# D2D-TOP.net
KiCad netlist of a schematic drawn in EAGLE
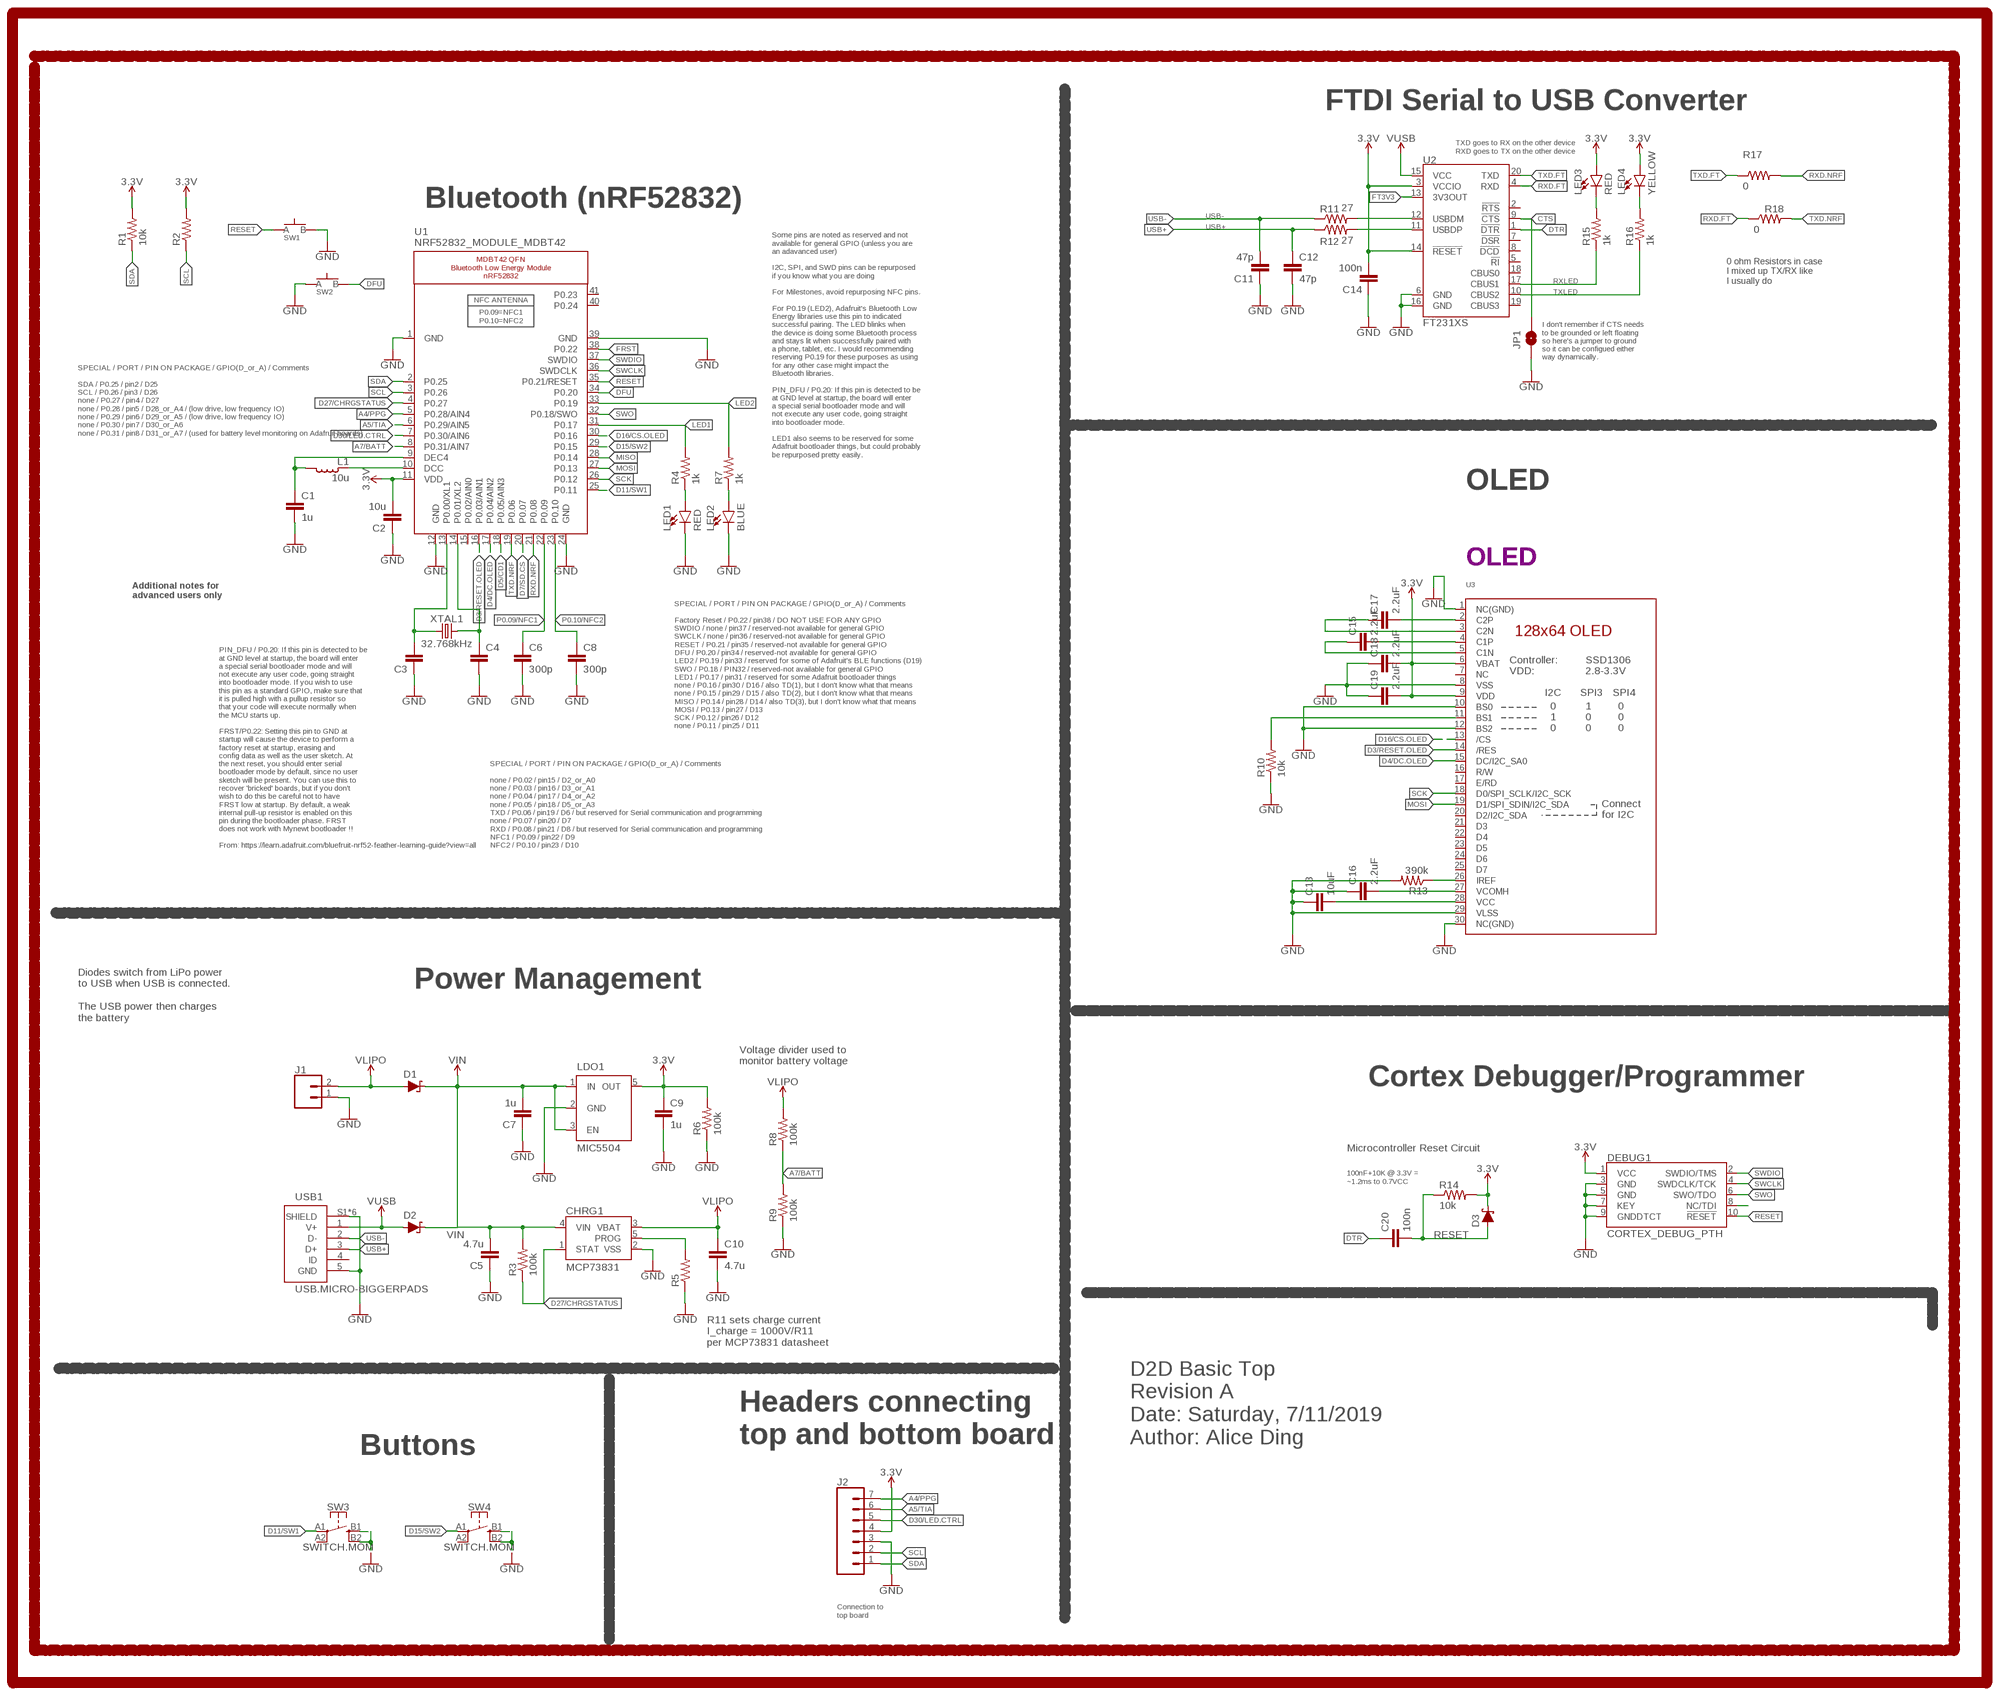
[diagram p0: schematic, sheet 1]

(export (version "E")
  (design (tool "Eeschema 10.0.6"))
  (components
    (comp (ref "C1")
      (value "1u")
      (footprint "eagle-import:C0603")
      (libsource (lib "eagle-import") (part "CAPACITOR0603"))
    )
    (comp (ref "C2")
      (value "10u")
      (footprint "eagle-import:C0805")
      (libsource (lib "eagle-import") (part "CAPACITOR0805"))
    )
    (comp (ref "C3")
      (value "CAPACITOR0603")
      (footprint "eagle-import:C0603")
      (libsource (lib "eagle-import") (part "CAPACITOR0603"))
    )
    (comp (ref "C4")
      (value "CAPACITOR0603")
      (footprint "eagle-import:C0603")
      (libsource (lib "eagle-import") (part "CAPACITOR0603"))
    )
    (comp (ref "C5")
      (value "4.7u")
      (footprint "eagle-import:C0603")
      (libsource (lib "eagle-import") (part "CAPACITOR0603"))
    )
    (comp (ref "C6")
      (value "300p")
      (footprint "eagle-import:C0603")
      (libsource (lib "eagle-import") (part "CAPACITOR0603"))
    )
    (comp (ref "C7")
      (value "1u")
      (footprint "eagle-import:C0603")
      (libsource (lib "eagle-import") (part "CAPACITOR0603"))
    )
    (comp (ref "C8")
      (value "300p")
      (footprint "eagle-import:C0603")
      (libsource (lib "eagle-import") (part "CAPACITOR0603"))
    )
    (comp (ref "C9")
      (value "1u")
      (footprint "eagle-import:C0603")
      (libsource (lib "eagle-import") (part "CAPACITOR0603"))
    )
    (comp (ref "C10")
      (value "4.7u")
      (footprint "eagle-import:C0603")
      (libsource (lib "eagle-import") (part "CAPACITOR0603"))
    )
    (comp (ref "C11")
      (value "47p")
      (footprint "eagle-import:C0603")
      (libsource (lib "eagle-import") (part "CAPACITOR0603"))
    )
    (comp (ref "C12")
      (value "47p")
      (footprint "eagle-import:C0603")
      (libsource (lib "eagle-import") (part "CAPACITOR0603"))
    )
    (comp (ref "C13")
      (value "10uF")
      (footprint "eagle-import:C0603")
      (libsource (lib "eagle-import") (part "CAPACITOR0603"))
    )
    (comp (ref "C14")
      (value "100n")
      (footprint "eagle-import:C0603")
      (libsource (lib "eagle-import") (part "CAPACITOR0603"))
    )
    (comp (ref "C15")
      (value "2.2uF")
      (footprint "eagle-import:C0402")
      (libsource (lib "eagle-import") (part "CAPACITOR0402"))
    )
    (comp (ref "C16")
      (value "2.2uF")
      (footprint "eagle-import:C0402")
      (libsource (lib "eagle-import") (part "CAPACITOR0402"))
    )
    (comp (ref "C17")
      (value "2.2uF")
      (footprint "eagle-import:C0402")
      (libsource (lib "eagle-import") (part "CAPACITOR0402"))
    )
    (comp (ref "C18")
      (value "2.2uF")
      (footprint "eagle-import:C0402")
      (libsource (lib "eagle-import") (part "CAPACITOR0402"))
    )
    (comp (ref "C19")
      (value "2.2uF")
      (footprint "eagle-import:C0402")
      (libsource (lib "eagle-import") (part "CAPACITOR0402"))
    )
    (comp (ref "C20")
      (value "100n")
      (footprint "eagle-import:C0603")
      (libsource (lib "eagle-import") (part "CAPACITOR0603"))
    )
    (comp (ref "CHRG1")
      (value "MCP73831")
      (footprint "eagle-import:SOT23-5")
      (libsource (lib "eagle-import") (part "MCP73831"))
    )
    (comp (ref "D1")
      (value "SCHOTTKY-USC")
      (footprint "eagle-import:USC")
      (libsource (lib "eagle-import") (part "SCHOTTKY-USC"))
    )
    (comp (ref "D2")
      (value "SCHOTTKY-USC")
      (footprint "eagle-import:USC")
      (libsource (lib "eagle-import") (part "SCHOTTKY-USC"))
    )
    (comp (ref "D3")
      (value "SCHOTTKY-USC")
      (footprint "eagle-import:USC")
      (libsource (lib "eagle-import") (part "SCHOTTKY-USC"))
    )
    (comp (ref "DEBUG1")
      (value "CORTEX_DEBUG_PTH")
      (footprint "eagle-import:2X5-PTH-1.27MM")
      (libsource (lib "eagle-import") (part "CORTEX_DEBUG_PTH"))
    )
    (comp (ref "J1")
      (value "CONN_02")
      (footprint "eagle-import:1X02")
      (libsource (lib "eagle-import") (part "CONN_02"))
    )
    (comp (ref "J2")
      (value "CONN_07-1.27MM")
      (footprint "eagle-import:1X07_1.27MM")
      (libsource (lib "eagle-import") (part "CONN_07-1.27MM"))
    )
    (comp (ref "JP1")
      (value "JUMPER-SMT_2_NO_SILK")
      (footprint "eagle-import:SMT-JUMPER_2_NO_SILK")
      (libsource (lib "eagle-import") (part "JUMPER-SMT_2_NO_SILK"))
    )
    (comp (ref "L1")
      (value "10u")
      (footprint "eagle-import:L0603")
      (libsource (lib "eagle-import") (part "INDUCTOR0603"))
    )
    (comp (ref "LDO1")
      (value "MIC5504")
      (footprint "eagle-import:SOT23-5")
      (libsource (lib "eagle-import") (part "MIC5504"))
    )
    (comp (ref "LED1")
      (value "RED")
      (footprint "eagle-import:LED-0603")
      (libsource (lib "eagle-import") (part "LED0603"))
    )
    (comp (ref "LED2")
      (value "BLUE")
      (footprint "eagle-import:LED-0603")
      (libsource (lib "eagle-import") (part "LED0603"))
    )
    (comp (ref "LED3")
      (value "RED")
      (footprint "eagle-import:LED-0603")
      (libsource (lib "eagle-import") (part "LED0603"))
    )
    (comp (ref "LED4")
      (value "YELLOW")
      (footprint "eagle-import:LED-0603")
      (libsource (lib "eagle-import") (part "LED0603"))
    )
    (comp (ref "R1")
      (value "10k")
      (footprint "eagle-import:R0603")
      (libsource (lib "eagle-import") (part "RESISTOR0603"))
    )
    (comp (ref "R2")
      (value "RESISTOR0603")
      (footprint "eagle-import:R0603")
      (libsource (lib "eagle-import") (part "RESISTOR0603"))
    )
    (comp (ref "R3")
      (value "100k")
      (footprint "eagle-import:R0603")
      (libsource (lib "eagle-import") (part "RESISTOR0603"))
    )
    (comp (ref "R4")
      (value "1k")
      (footprint "eagle-import:R0603")
      (libsource (lib "eagle-import") (part "RESISTOR0603"))
    )
    (comp (ref "R5")
      (value "RESISTOR0603")
      (footprint "eagle-import:R0603")
      (libsource (lib "eagle-import") (part "RESISTOR0603"))
    )
    (comp (ref "R6")
      (value "100k")
      (footprint "eagle-import:R0603")
      (libsource (lib "eagle-import") (part "RESISTOR0603"))
    )
    (comp (ref "R7")
      (value "1k")
      (footprint "eagle-import:R0603")
      (libsource (lib "eagle-import") (part "RESISTOR0603"))
    )
    (comp (ref "R8")
      (value "100k")
      (footprint "eagle-import:R0603")
      (libsource (lib "eagle-import") (part "RESISTOR0603"))
    )
    (comp (ref "R9")
      (value "100k")
      (footprint "eagle-import:R0603")
      (libsource (lib "eagle-import") (part "RESISTOR0603"))
    )
    (comp (ref "R10")
      (value "10k")
      (footprint "eagle-import:R0603")
      (libsource (lib "eagle-import") (part "RESISTOR0603"))
    )
    (comp (ref "R11")
      (value "27")
      (footprint "eagle-import:R0603")
      (libsource (lib "eagle-import") (part "RESISTOR0603"))
    )
    (comp (ref "R12")
      (value "27")
      (footprint "eagle-import:R0603")
      (libsource (lib "eagle-import") (part "RESISTOR0603"))
    )
    (comp (ref "R13")
      (value "390k")
      (footprint "eagle-import:R0603")
      (libsource (lib "eagle-import") (part "RESISTOR0603"))
    )
    (comp (ref "R14")
      (value "10k")
      (footprint "eagle-import:R0603")
      (libsource (lib "eagle-import") (part "RESISTOR0603"))
    )
    (comp (ref "R15")
      (value "1k")
      (footprint "eagle-import:R0603")
      (libsource (lib "eagle-import") (part "RESISTOR0603"))
    )
    (comp (ref "R16")
      (value "1k")
      (footprint "eagle-import:R0603")
      (libsource (lib "eagle-import") (part "RESISTOR0603"))
    )
    (comp (ref "R17")
      (value "0")
      (footprint "eagle-import:R0603")
      (libsource (lib "eagle-import") (part "RESISTOR0603"))
    )
    (comp (ref "R18")
      (value "0")
      (footprint "eagle-import:R0603")
      (libsource (lib "eagle-import") (part "RESISTOR0603"))
    )
    (comp (ref "SW1")
      (value "SPST-PTS830GG140-COPY.1-3")
      (footprint "eagle-import:BUTTON-GULLWING")
      (libsource (lib "eagle-import") (part "SPST-PTS830GG140-COPY.1-3"))
    )
    (comp (ref "SW2")
      (value "SPST-PTS830GG140-COPY.1-3")
      (footprint "eagle-import:BUTTON-GULLWING")
      (libsource (lib "eagle-import") (part "SPST-PTS830GG140-COPY.1-3"))
    )
    (comp (ref "SW3")
      (value "SWITCH.MOM")
      (footprint "eagle-import:TACTILE_SWITCH_SMD_6.2MM_TALL")
      (libsource (lib "eagle-import") (part "SWITCH.MOM"))
    )
    (comp (ref "SW4")
      (value "SWITCH.MOM")
      (footprint "eagle-import:TACTILE_SWITCH_SMD_6.2MM_TALL")
      (libsource (lib "eagle-import") (part "SWITCH.MOM"))
    )
    (comp (ref "U1")
      (value "NRF52832_MODULE_MDBT42")
      (footprint "eagle-import:BLE_MODULE_RAYTAC_MDBT42")
      (libsource (lib "eagle-import") (part "NRF52832_MODULE_MDBT42"))
    )
    (comp (ref "U2")
      (value "FT231XS")
      (footprint "eagle-import:SSOP20_L")
      (libsource (lib "eagle-import") (part "FT231XS"))
    )
    (comp (ref "U3")
      (value "DISP_OLED_UG-2864HSWEG01-NO-WRAPAROUND")
      (footprint "eagle-import:UG-2864HSWEG01_0.96IN_NO-WRAPAROUND")
      (libsource (lib "eagle-import") (part "DISP_OLED_UG-2864HSWEG01-NO-WRAPAROUND"))
    )
    (comp (ref "USB1")
      (value "USB.MICRO-BIGGERPADS")
      (footprint "eagle-import:USB-MICRO-01.BIGGERPADS")
      (libsource (lib "eagle-import") (part "USB.MICRO-BIGGERPADS"))
    )
    (comp (ref "XTAL1")
      (value "32.768kHz")
      (footprint "eagle-import:2-SMD.NOLEAD.2.0MMTO1.2MM")
      (libsource (lib "eagle-import") (part "CRYSTALECS-.327-12.5-12-C-TR"))
    )
  )
  (nets
    (net (code "1") (name "/RXLED") (class "Default")
      (node (ref "R15") (pin "1") (pinfunction "1_1") (pintype "passive"))
      (node (ref "U2") (pin "17") (pinfunction "CBUS1_17") (pintype "bidirectional"))
    )
    (net (code "2") (name "/TXLED") (class "Default")
      (node (ref "R16") (pin "1") (pinfunction "1_1") (pintype "passive"))
      (node (ref "U2") (pin "10") (pinfunction "CBUS2_10") (pintype "bidirectional"))
    )
    (net (code "3") (name "3.3V") (class "Default")
      (node (ref "C14") (pin "2") (pinfunction "2_2") (pintype "passive"))
      (node (ref "C18") (pin "2") (pinfunction "2_2") (pintype "passive"))
      (node (ref "C19") (pin "2") (pinfunction "2_2") (pintype "passive"))
      (node (ref "C2") (pin "2") (pinfunction "2_2") (pintype "passive"))
      (node (ref "C9") (pin "1") (pinfunction "1_1") (pintype "passive"))
      (node (ref "D3") (pin "-") (pinfunction "C_-") (pintype "passive"))
      (node (ref "DEBUG1") (pin "1") (pinfunction "VCC_1") (pintype "bidirectional"))
      (node (ref "J2") (pin "4") (pinfunction "4_4") (pintype "passive"))
      (node (ref "LDO1") (pin "5") (pinfunction "OUT_5") (pintype "bidirectional"))
      (node (ref "LED3") (pin "A") (pinfunction "A_A") (pintype "passive"))
      (node (ref "LED4") (pin "A") (pinfunction "A_A") (pintype "passive"))
      (node (ref "R1") (pin "2") (pinfunction "2_2") (pintype "passive"))
      (node (ref "R14") (pin "2") (pinfunction "2_2") (pintype "passive"))
      (node (ref "R2") (pin "2") (pinfunction "2_2") (pintype "passive"))
      (node (ref "R6") (pin "2") (pinfunction "2_2") (pintype "passive"))
      (node (ref "U1") (pin "11") (pinfunction "VDD_11") (pintype "bidirectional"))
      (node (ref "U2") (pin "14") (pinfunction "~{RESET}_14") (pintype "bidirectional"))
      (node (ref "U2") (pin "3") (pinfunction "VCCIO_3") (pintype "bidirectional"))
      (node (ref "U3") (pin "6") (pinfunction "VBAT_6") (pintype "input"))
      (node (ref "U3") (pin "9") (pinfunction "VDD_9") (pintype "power_in"))
    )
    (net (code "4") (name "A4{slash}PPG") (class "Default")
      (node (ref "J2") (pin "7") (pinfunction "7_7") (pintype "passive"))
      (node (ref "U1") (pin "5") (pinfunction "P0.28/AIN4_5") (pintype "bidirectional"))
    )
    (net (code "5") (name "A5{slash}TIA") (class "Default")
      (node (ref "J2") (pin "6") (pinfunction "6_6") (pintype "passive"))
      (node (ref "U1") (pin "6") (pinfunction "P0.29/AIN5_6") (pintype "bidirectional"))
    )
    (net (code "6") (name "A7{slash}BATT") (class "Default")
      (node (ref "R8") (pin "1") (pinfunction "1_1") (pintype "passive"))
      (node (ref "R9") (pin "2") (pinfunction "2_2") (pintype "passive"))
      (node (ref "U1") (pin "8") (pinfunction "P0.31/AIN7_8") (pintype "bidirectional"))
    )
    (net (code "7") (name "CTS") (class "Default")
      (node (ref "JP1") (pin "2") (pinfunction "2_2") (pintype "passive"))
      (node (ref "U2") (pin "9") (pinfunction "~{CTS}_9") (pintype "bidirectional"))
    )
    (net (code "8") (name "D3{slash}RESET.OLED") (class "Default")
      (node (ref "U1") (pin "16") (pinfunction "P0.03/AIN1_16") (pintype "bidirectional"))
      (node (ref "U3") (pin "14") (pinfunction "/RES_14") (pintype "input"))
    )
    (net (code "9") (name "D4{slash}DC.OLED") (class "Default")
      (node (ref "U1") (pin "17") (pinfunction "P0.04/AIN2_17") (pintype "bidirectional"))
      (node (ref "U3") (pin "15") (pinfunction "DC/I2C_SA0_15") (pintype "input"))
    )
    (net (code "10") (name "D5{slash}CD1") (class "Default")
      (node (ref "U1") (pin "18") (pinfunction "P0.05/AIN3_18") (pintype "bidirectional"))
    )
    (net (code "11") (name "D7{slash}SD.CS") (class "Default")
      (node (ref "U1") (pin "20") (pinfunction "P0.07_20") (pintype "bidirectional"))
    )
    (net (code "12") (name "D11{slash}SW1") (class "Default")
      (node (ref "SW3") (pin "A1") (pinfunction "1_A1") (pintype "passive"))
      (node (ref "U1") (pin "25") (pinfunction "P0.11_25") (pintype "bidirectional"))
    )
    (net (code "13") (name "D15{slash}SW2") (class "Default")
      (node (ref "SW4") (pin "A1") (pinfunction "1_A1") (pintype "passive"))
      (node (ref "U1") (pin "29") (pinfunction "P0.15_29") (pintype "bidirectional"))
    )
    (net (code "14") (name "D16{slash}CS.OLED") (class "Default")
      (node (ref "U1") (pin "30") (pinfunction "P0.16_30") (pintype "bidirectional"))
      (node (ref "U3") (pin "13") (pinfunction "/CS_13") (pintype "input"))
    )
    (net (code "15") (name "D27{slash}CHRGSTATUS") (class "Default")
      (node (ref "CHRG1") (pin "1") (pinfunction "STAT_1") (pintype "output"))
      (node (ref "R3") (pin "1") (pinfunction "1_1") (pintype "passive"))
      (node (ref "U1") (pin "4") (pinfunction "P0.27_4") (pintype "bidirectional"))
    )
    (net (code "16") (name "D30{slash}LED.CTRL") (class "Default")
      (node (ref "J2") (pin "5") (pinfunction "5_5") (pintype "passive"))
      (node (ref "U1") (pin "7") (pinfunction "P0.30/AIN6_7") (pintype "bidirectional"))
    )
    (net (code "17") (name "DFU") (class "Default")
      (node (ref "SW2") (pin "3") (pinfunction "B_3") (pintype "bidirectional"))
      (node (ref "U1") (pin "34") (pinfunction "P0.20_34") (pintype "bidirectional"))
    )
    (net (code "18") (name "DTR") (class "Default")
      (node (ref "C20") (pin "1") (pinfunction "1_1") (pintype "passive"))
      (node (ref "U2") (pin "1") (pinfunction "~{DTR}_1") (pintype "bidirectional"))
    )
    (net (code "19") (name "FRST") (class "Default")
      (node (ref "U1") (pin "38") (pinfunction "P0.22_38") (pintype "bidirectional"))
    )
    (net (code "20") (name "FT3V3") (class "Default")
      (node (ref "U2") (pin "13") (pinfunction "3V3OUT_13") (pintype "bidirectional"))
    )
    (net (code "21") (name "GND") (class "Default")
      (node (ref "C1") (pin "2") (pinfunction "2_2") (pintype "passive"))
      (node (ref "C10") (pin "2") (pinfunction "2_2") (pintype "passive"))
      (node (ref "C11") (pin "1") (pinfunction "1_1") (pintype "passive"))
      (node (ref "C12") (pin "2") (pinfunction "2_2") (pintype "passive"))
      (node (ref "C13") (pin "1") (pinfunction "1_1") (pintype "passive"))
      (node (ref "C14") (pin "1") (pinfunction "1_1") (pintype "passive"))
      (node (ref "C16") (pin "1") (pinfunction "1_1") (pintype "passive"))
      (node (ref "C18") (pin "1") (pinfunction "1_1") (pintype "passive"))
      (node (ref "C19") (pin "1") (pinfunction "1_1") (pintype "passive"))
      (node (ref "C2") (pin "1") (pinfunction "1_1") (pintype "passive"))
      (node (ref "C3") (pin "1") (pinfunction "1_1") (pintype "passive"))
      (node (ref "C4") (pin "2") (pinfunction "2_2") (pintype "passive"))
      (node (ref "C5") (pin "1") (pinfunction "1_1") (pintype "passive"))
      (node (ref "C6") (pin "2") (pinfunction "2_2") (pintype "passive"))
      (node (ref "C7") (pin "1") (pinfunction "1_1") (pintype "passive"))
      (node (ref "C8") (pin "2") (pinfunction "2_2") (pintype "passive"))
      (node (ref "C9") (pin "2") (pinfunction "2_2") (pintype "passive"))
      (node (ref "CHRG1") (pin "2") (pinfunction "VSS_2") (pintype "power_in"))
      (node (ref "DEBUG1") (pin "3") (pinfunction "GND_3") (pintype "bidirectional"))
      (node (ref "DEBUG1") (pin "5") (pinfunction "GND_5") (pintype "bidirectional"))
      (node (ref "DEBUG1") (pin "7") (pinfunction "KEY_7") (pintype "bidirectional"))
      (node (ref "DEBUG1") (pin "9") (pinfunction "GNDDTCT_9") (pintype "bidirectional"))
      (node (ref "J1") (pin "1") (pinfunction "1_1") (pintype "passive"))
      (node (ref "J2") (pin "3") (pinfunction "3_3") (pintype "passive"))
      (node (ref "JP1") (pin "1") (pinfunction "1_1") (pintype "passive"))
      (node (ref "LDO1") (pin "2") (pinfunction "GND_2") (pintype "bidirectional"))
      (node (ref "LED1") (pin "C") (pinfunction "C_C") (pintype "passive"))
      (node (ref "LED2") (pin "C") (pinfunction "C_C") (pintype "passive"))
      (node (ref "R10") (pin "1") (pinfunction "1_1") (pintype "passive"))
      (node (ref "R13") (pin "2") (pinfunction "2_2") (pintype "passive"))
      (node (ref "R5") (pin "1") (pinfunction "1_1") (pintype "passive"))
      (node (ref "R6") (pin "1") (pinfunction "1_1") (pintype "passive"))
      (node (ref "R9") (pin "1") (pinfunction "1_1") (pintype "passive"))
      (node (ref "SW1") (pin "3") (pinfunction "B_3") (pintype "bidirectional"))
      (node (ref "SW2") (pin "1") (pinfunction "A_1") (pintype "bidirectional"))
      (node (ref "SW3") (pin "B1") (pinfunction "3_B1") (pintype "passive"))
      (node (ref "SW3") (pin "B2") (pinfunction "4_B2") (pintype "passive"))
      (node (ref "SW4") (pin "B1") (pinfunction "3_B1") (pintype "passive"))
      (node (ref "SW4") (pin "B2") (pinfunction "4_B2") (pintype "passive"))
      (node (ref "U1") (pin "1") (pinfunction "GND_1") (pintype "bidirectional"))
      (node (ref "U1") (pin "12") (pinfunction "GND_12") (pintype "bidirectional"))
      (node (ref "U1") (pin "24") (pinfunction "GND_24") (pintype "bidirectional"))
      (node (ref "U1") (pin "39") (pinfunction "GND_39") (pintype "bidirectional"))
      (node (ref "U2") (pin "16") (pinfunction "GND_16") (pintype "bidirectional"))
      (node (ref "U2") (pin "6") (pinfunction "GND_6") (pintype "bidirectional"))
      (node (ref "U3") (pin "1") (pinfunction "NC(GND)_1") (pintype "input"))
      (node (ref "U3") (pin "10") (pinfunction "BS0_10") (pintype "input"))
      (node (ref "U3") (pin "12") (pinfunction "BS2_12") (pintype "input"))
      (node (ref "U3") (pin "29") (pinfunction "VLSS_29") (pintype "power_in"))
      (node (ref "U3") (pin "30") (pinfunction "NC(GND)_30") (pintype "input"))
      (node (ref "U3") (pin "8") (pinfunction "VSS_8") (pintype "power_in"))
      (node (ref "USB1") (pin "5") (pinfunction "GND_5") (pintype "bidirectional"))
      (node (ref "USB1") (pin "S1") (pinfunction "SHIELD_S1") (pintype "bidirectional"))
      (node (ref "USB1") (pin "S2") (pinfunction "SHIELD_S2") (pintype "bidirectional"))
      (node (ref "USB1") (pin "S3") (pinfunction "SHIELD_S3") (pintype "bidirectional"))
      (node (ref "USB1") (pin "S4") (pinfunction "SHIELD_S4") (pintype "bidirectional"))
      (node (ref "USB1") (pin "S5") (pinfunction "SHIELD_S5") (pintype "bidirectional"))
      (node (ref "USB1") (pin "S6") (pinfunction "SHIELD_S6") (pintype "bidirectional"))
    )
    (net (code "22") (name "LED1") (class "Default")
      (node (ref "R4") (pin "2") (pinfunction "2_2") (pintype "passive"))
      (node (ref "U1") (pin "31") (pinfunction "P0.17_31") (pintype "bidirectional"))
    )
    (net (code "23") (name "LED2") (class "Default")
      (node (ref "R7") (pin "2") (pinfunction "2_2") (pintype "passive"))
      (node (ref "U1") (pin "33") (pinfunction "P0.19_33") (pintype "bidirectional"))
    )
    (net (code "24") (name "MISO") (class "Default")
      (node (ref "U1") (pin "28") (pinfunction "P0.14_28") (pintype "bidirectional"))
    )
    (net (code "25") (name "MOSI") (class "Default")
      (node (ref "U1") (pin "27") (pinfunction "P0.13_27") (pintype "bidirectional"))
      (node (ref "U3") (pin "19") (pinfunction "D1/SPI_SDIN/I2C_SDA_19") (pintype "bidirectional"))
    )
    (net (code "26") (name "Net-(CHRG1-PROG)") (class "Default")
      (node (ref "CHRG1") (pin "5") (pinfunction "PROG_5") (pintype "input"))
      (node (ref "R5") (pin "2") (pinfunction "2_2") (pintype "passive"))
    )
    (net (code "27") (name "Net-(LED1-PadA)") (class "Default")
      (node (ref "LED1") (pin "A") (pinfunction "A_A") (pintype "passive"))
      (node (ref "R4") (pin "1") (pinfunction "1_1") (pintype "passive"))
    )
    (net (code "28") (name "Net-(LED2-PadA)") (class "Default")
      (node (ref "LED2") (pin "A") (pinfunction "A_A") (pintype "passive"))
      (node (ref "R7") (pin "1") (pinfunction "1_1") (pintype "passive"))
    )
    (net (code "29") (name "Net-(LED3-PadC)") (class "Default")
      (node (ref "LED3") (pin "C") (pinfunction "C_C") (pintype "passive"))
      (node (ref "R15") (pin "2") (pinfunction "2_2") (pintype "passive"))
    )
    (net (code "30") (name "Net-(LED4-PadC)") (class "Default")
      (node (ref "LED4") (pin "C") (pinfunction "C_C") (pintype "passive"))
      (node (ref "R16") (pin "2") (pinfunction "2_2") (pintype "passive"))
    )
    (net (code "31") (name "Net-(U1-DCC)") (class "Default")
      (node (ref "L1") (pin "1") (pinfunction "1_1") (pintype "passive"))
      (node (ref "U1") (pin "10") (pinfunction "DCC_10") (pintype "bidirectional"))
    )
    (net (code "32") (name "Net-(U1-DEC4)") (class "Default")
      (node (ref "C1") (pin "1") (pinfunction "1_1") (pintype "passive"))
      (node (ref "L1") (pin "2") (pinfunction "2_2") (pintype "passive"))
      (node (ref "U1") (pin "9") (pinfunction "DEC4_9") (pintype "bidirectional"))
    )
    (net (code "33") (name "Net-(U1-P0.00{slash}XL1)") (class "Default")
      (node (ref "C3") (pin "2") (pinfunction "2_2") (pintype "passive"))
      (node (ref "U1") (pin "13") (pinfunction "P0.00/XL1_13") (pintype "bidirectional"))
      (node (ref "XTAL1") (pin "P$1") (pinfunction "1_P$1") (pintype "passive"))
    )
    (net (code "34") (name "Net-(U1-P0.01{slash}XL2)") (class "Default")
      (node (ref "C4") (pin "1") (pinfunction "1_1") (pintype "passive"))
      (node (ref "U1") (pin "14") (pinfunction "P0.01/XL2_14") (pintype "bidirectional"))
      (node (ref "XTAL1") (pin "P$2") (pinfunction "2_P$2") (pintype "passive"))
    )
    (net (code "35") (name "Net-(U2-USBDM)") (class "Default")
      (node (ref "R11") (pin "2") (pinfunction "2_2") (pintype "passive"))
      (node (ref "U2") (pin "12") (pinfunction "USBDM_12") (pintype "bidirectional"))
    )
    (net (code "36") (name "Net-(U2-USBDP)") (class "Default")
      (node (ref "R12") (pin "2") (pinfunction "2_2") (pintype "passive"))
      (node (ref "U2") (pin "11") (pinfunction "USBDP_11") (pintype "bidirectional"))
    )
    (net (code "37") (name "Net-(U3-BS1)") (class "Default")
      (node (ref "R10") (pin "2") (pinfunction "2_2") (pintype "passive"))
      (node (ref "U3") (pin "11") (pinfunction "BS1_11") (pintype "input"))
    )
    (net (code "38") (name "Net-(U3-C1N)") (class "Default")
      (node (ref "C15") (pin "1") (pinfunction "1_1") (pintype "passive"))
      (node (ref "U3") (pin "5") (pinfunction "C1N_5") (pintype "input"))
    )
    (net (code "39") (name "Net-(U3-C1P)") (class "Default")
      (node (ref "C15") (pin "2") (pinfunction "2_2") (pintype "passive"))
      (node (ref "U3") (pin "4") (pinfunction "C1P_4") (pintype "input"))
    )
    (net (code "40") (name "Net-(U3-C2N)") (class "Default")
      (node (ref "C17") (pin "1") (pinfunction "1_1") (pintype "passive"))
      (node (ref "U3") (pin "3") (pinfunction "C2N_3") (pintype "input"))
    )
    (net (code "41") (name "Net-(U3-C2P)") (class "Default")
      (node (ref "C17") (pin "2") (pinfunction "2_2") (pintype "passive"))
      (node (ref "U3") (pin "2") (pinfunction "C2P_2") (pintype "input"))
    )
    (net (code "42") (name "Net-(U3-IREF)") (class "Default")
      (node (ref "R13") (pin "1") (pinfunction "1_1") (pintype "passive"))
      (node (ref "U3") (pin "26") (pinfunction "IREF_26") (pintype "input"))
    )
    (net (code "43") (name "Net-(U3-VCC)") (class "Default")
      (node (ref "C13") (pin "2") (pinfunction "2_2") (pintype "passive"))
      (node (ref "U3") (pin "28") (pinfunction "VCC_28") (pintype "power_in"))
    )
    (net (code "44") (name "Net-(U3-VCOMH)") (class "Default")
      (node (ref "C16") (pin "2") (pinfunction "2_2") (pintype "passive"))
      (node (ref "U3") (pin "27") (pinfunction "VCOMH_27") (pintype "output"))
    )
    (net (code "45") (name "P0.09{slash}NFC1") (class "Default")
      (node (ref "C6") (pin "1") (pinfunction "1_1") (pintype "passive"))
      (node (ref "U1") (pin "22") (pinfunction "P0.09_22") (pintype "bidirectional"))
    )
    (net (code "46") (name "P0.10{slash}NFC2") (class "Default")
      (node (ref "C8") (pin "1") (pinfunction "1_1") (pintype "passive"))
      (node (ref "U1") (pin "23") (pinfunction "P0.10_23") (pintype "bidirectional"))
    )
    (net (code "47") (name "RESET") (class "Default")
      (node (ref "C20") (pin "2") (pinfunction "2_2") (pintype "passive"))
      (node (ref "D3") (pin "+") (pinfunction "A_+") (pintype "passive"))
      (node (ref "DEBUG1") (pin "10") (pinfunction "~{RESET}_10") (pintype "bidirectional"))
      (node (ref "R14") (pin "1") (pinfunction "1_1") (pintype "passive"))
      (node (ref "SW1") (pin "1") (pinfunction "A_1") (pintype "bidirectional"))
      (node (ref "U1") (pin "35") (pinfunction "P0.21/RESET_35") (pintype "bidirectional"))
    )
    (net (code "48") (name "RXD.FT") (class "Default")
      (node (ref "R18") (pin "1") (pinfunction "1_1") (pintype "passive"))
      (node (ref "U2") (pin "4") (pinfunction "RXD_4") (pintype "bidirectional"))
    )
    (net (code "49") (name "RXD.NRF") (class "Default")
      (node (ref "R17") (pin "2") (pinfunction "2_2") (pintype "passive"))
      (node (ref "U1") (pin "21") (pinfunction "P0.08_21") (pintype "bidirectional"))
    )
    (net (code "50") (name "SCK") (class "Default")
      (node (ref "U1") (pin "26") (pinfunction "P0.12_26") (pintype "bidirectional"))
      (node (ref "U3") (pin "18") (pinfunction "D0/SPI_SCLK/I2C_SCK_18") (pintype "bidirectional"))
    )
    (net (code "51") (name "SCL") (class "Default")
      (node (ref "J2") (pin "2") (pinfunction "2_2") (pintype "passive"))
      (node (ref "R2") (pin "1") (pinfunction "1_1") (pintype "passive"))
      (node (ref "U1") (pin "3") (pinfunction "P0.26_3") (pintype "bidirectional"))
    )
    (net (code "52") (name "SDA") (class "Default")
      (node (ref "J2") (pin "1") (pinfunction "1_1") (pintype "passive"))
      (node (ref "R1") (pin "1") (pinfunction "1_1") (pintype "passive"))
      (node (ref "U1") (pin "2") (pinfunction "P0.25_2") (pintype "bidirectional"))
    )
    (net (code "53") (name "SWCLK") (class "Default")
      (node (ref "DEBUG1") (pin "4") (pinfunction "SWDCLK/TCK_4") (pintype "bidirectional"))
      (node (ref "U1") (pin "36") (pinfunction "SWDCLK_36") (pintype "bidirectional"))
    )
    (net (code "54") (name "SWDIO") (class "Default")
      (node (ref "DEBUG1") (pin "2") (pinfunction "SWDIO/TMS_2") (pintype "bidirectional"))
      (node (ref "U1") (pin "37") (pinfunction "SWDIO_37") (pintype "bidirectional"))
    )
    (net (code "55") (name "SWO") (class "Default")
      (node (ref "DEBUG1") (pin "6") (pinfunction "SWO/TDO_6") (pintype "bidirectional"))
      (node (ref "U1") (pin "32") (pinfunction "P0.18/SWO_32") (pintype "bidirectional"))
    )
    (net (code "56") (name "TXD.FT") (class "Default")
      (node (ref "R17") (pin "1") (pinfunction "1_1") (pintype "passive"))
      (node (ref "U2") (pin "20") (pinfunction "TXD_20") (pintype "bidirectional"))
    )
    (net (code "57") (name "TXD.NRF") (class "Default")
      (node (ref "R18") (pin "2") (pinfunction "2_2") (pintype "passive"))
      (node (ref "U1") (pin "19") (pinfunction "P0.06_19") (pintype "bidirectional"))
    )
    (net (code "58") (name "USB+") (class "Default")
      (node (ref "C12") (pin "1") (pinfunction "1_1") (pintype "passive"))
      (node (ref "R12") (pin "1") (pinfunction "1_1") (pintype "passive"))
      (node (ref "USB1") (pin "3") (pinfunction "D+_3") (pintype "bidirectional"))
    )
    (net (code "59") (name "USB-") (class "Default")
      (node (ref "C11") (pin "2") (pinfunction "2_2") (pintype "passive"))
      (node (ref "R11") (pin "1") (pinfunction "1_1") (pintype "passive"))
      (node (ref "USB1") (pin "2") (pinfunction "D-_2") (pintype "bidirectional"))
    )
    (net (code "60") (name "VIN") (class "Default")
      (node (ref "C5") (pin "2") (pinfunction "2_2") (pintype "passive"))
      (node (ref "C7") (pin "2") (pinfunction "2_2") (pintype "passive"))
      (node (ref "CHRG1") (pin "4") (pinfunction "VIN_4") (pintype "power_in"))
      (node (ref "D1") (pin "-") (pinfunction "C_-") (pintype "passive"))
      (node (ref "D2") (pin "-") (pinfunction "C_-") (pintype "passive"))
      (node (ref "LDO1") (pin "1") (pinfunction "IN_1") (pintype "bidirectional"))
      (node (ref "LDO1") (pin "3") (pinfunction "EN_3") (pintype "bidirectional"))
      (node (ref "R3") (pin "2") (pinfunction "2_2") (pintype "passive"))
    )
    (net (code "61") (name "VLIPO") (class "Default")
      (node (ref "C10") (pin "1") (pinfunction "1_1") (pintype "passive"))
      (node (ref "CHRG1") (pin "3") (pinfunction "VBAT_3") (pintype "power_in"))
      (node (ref "D1") (pin "+") (pinfunction "A_+") (pintype "passive"))
      (node (ref "J1") (pin "2") (pinfunction "2_2") (pintype "passive"))
      (node (ref "R8") (pin "2") (pinfunction "2_2") (pintype "passive"))
    )
    (net (code "62") (name "VUSB") (class "Default")
      (node (ref "D2") (pin "+") (pinfunction "A_+") (pintype "passive"))
      (node (ref "U2") (pin "15") (pinfunction "VCC_15") (pintype "bidirectional"))
      (node (ref "USB1") (pin "1") (pinfunction "V+_1") (pintype "bidirectional"))
    )
    (net (code "63") (name "unconnected-(DEBUG1-NC{slash}TDI-Pad8)") (class "Default")
      (node (ref "DEBUG1") (pin "8") (pinfunction "NC/TDI_8") (pintype "bidirectional"))
    )
    (net (code "64") (name "unconnected-(SW3-2-PadA2)") (class "Default")
      (node (ref "SW3") (pin "A2") (pinfunction "2_A2") (pintype "passive"))
    )
    (net (code "65") (name "unconnected-(SW4-2-PadA2)") (class "Default")
      (node (ref "SW4") (pin "A2") (pinfunction "2_A2") (pintype "passive"))
    )
    (net (code "66") (name "unconnected-(U1-P0.02{slash}AIN0-Pad15)") (class "Default")
      (node (ref "U1") (pin "15") (pinfunction "P0.02/AIN0_15") (pintype "bidirectional"))
    )
    (net (code "67") (name "unconnected-(U1-P0.23-Pad41)") (class "Default")
      (node (ref "U1") (pin "41") (pinfunction "P0.23_41") (pintype "bidirectional"))
    )
    (net (code "68") (name "unconnected-(U1-P0.24-Pad40)") (class "Default")
      (node (ref "U1") (pin "40") (pinfunction "P0.24_40") (pintype "bidirectional"))
    )
    (net (code "69") (name "unconnected-(U2-CBUS0-Pad18)") (class "Default")
      (node (ref "U2") (pin "18") (pinfunction "CBUS0_18") (pintype "bidirectional"))
    )
    (net (code "70") (name "unconnected-(U2-CBUS3-Pad19)") (class "Default")
      (node (ref "U2") (pin "19") (pinfunction "CBUS3_19") (pintype "bidirectional"))
    )
    (net (code "71") (name "unconnected-(U2-~{DCD}-Pad8)") (class "Default")
      (node (ref "U2") (pin "8") (pinfunction "~{DCD}_8") (pintype "bidirectional"))
    )
    (net (code "72") (name "unconnected-(U2-~{DSR}-Pad7)") (class "Default")
      (node (ref "U2") (pin "7") (pinfunction "~{DSR}_7") (pintype "bidirectional"))
    )
    (net (code "73") (name "unconnected-(U2-~{RI}-Pad5)") (class "Default")
      (node (ref "U2") (pin "5") (pinfunction "~{RI}_5") (pintype "bidirectional"))
    )
    (net (code "74") (name "unconnected-(U2-~{RTS}-Pad2)") (class "Default")
      (node (ref "U2") (pin "2") (pinfunction "~{RTS}_2") (pintype "bidirectional"))
    )
    (net (code "75") (name "unconnected-(U3-D2{slash}I2C_SDA-Pad20)") (class "Default")
      (node (ref "U3") (pin "20") (pinfunction "D2/I2C_SDA_20") (pintype "bidirectional"))
    )
    (net (code "76") (name "unconnected-(U3-D3-Pad21)") (class "Default")
      (node (ref "U3") (pin "21") (pinfunction "D3_21") (pintype "bidirectional"))
    )
    (net (code "77") (name "unconnected-(U3-D4-Pad22)") (class "Default")
      (node (ref "U3") (pin "22") (pinfunction "D4_22") (pintype "bidirectional"))
    )
    (net (code "78") (name "unconnected-(U3-D5-Pad23)") (class "Default")
      (node (ref "U3") (pin "23") (pinfunction "D5_23") (pintype "bidirectional"))
    )
    (net (code "79") (name "unconnected-(U3-D6-Pad24)") (class "Default")
      (node (ref "U3") (pin "24") (pinfunction "D6_24") (pintype "bidirectional"))
    )
    (net (code "80") (name "unconnected-(U3-D7-Pad25)") (class "Default")
      (node (ref "U3") (pin "25") (pinfunction "D7_25") (pintype "bidirectional"))
    )
    (net (code "81") (name "unconnected-(U3-E{slash}RD-Pad17)") (class "Default")
      (node (ref "U3") (pin "17") (pinfunction "E/RD_17") (pintype "input"))
    )
    (net (code "82") (name "unconnected-(U3-NC-Pad7)") (class "Default")
      (node (ref "U3") (pin "7") (pinfunction "NC_7") (pintype "no_connect"))
    )
    (net (code "83") (name "unconnected-(U3-R{slash}W-Pad16)") (class "Default")
      (node (ref "U3") (pin "16") (pinfunction "R/W_16") (pintype "input"))
    )
    (net (code "84") (name "unconnected-(USB1-ID-Pad4)") (class "Default")
      (node (ref "USB1") (pin "4") (pinfunction "ID_4") (pintype "bidirectional"))
    )
  )
)
